# SOT23-3_to_AVR_Parttester.net
KiCad netlist of a schematic drawn in EAGLE
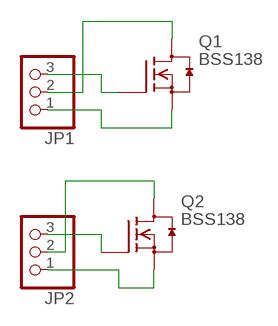
[diagram p0: schematic, sheet 1]

(export (version "E")
  (design (tool "Eeschema 10.0.6"))
  (components
    (comp (ref "JP1")
      (value "PINHD-1X3")
      (footprint "eagle-import:1X03")
      (libsource (lib "eagle-import") (part "PINHD-1X3"))
    )
    (comp (ref "JP2")
      (value "PINHD-1X3")
      (footprint "eagle-import:1X03")
      (libsource (lib "eagle-import") (part "PINHD-1X3"))
    )
    (comp (ref "Q1")
      (value "BSS138")
      (footprint "eagle-import:SOT23")
      (libsource (lib "eagle-import") (part "BSS138"))
    )
    (comp (ref "Q2")
      (value "BSS138")
      (footprint "eagle-import:SOT23")
      (libsource (lib "eagle-import") (part "BSS138"))
    )
  )
  (nets
    (net (code "1") (name "Net-(Q1-D)") (class "Default")
      (node (ref "JP1") (pin "2") (pinfunction "2_2") (pintype "passive"))
      (node (ref "Q1") (pin "3") (pinfunction "D_3") (pintype "passive"))
    )
    (net (code "2") (name "Net-(Q1-G)") (class "Default")
      (node (ref "JP1") (pin "3") (pinfunction "3_3") (pintype "passive"))
      (node (ref "Q1") (pin "1") (pinfunction "G_1") (pintype "passive"))
    )
    (net (code "3") (name "Net-(Q1-S)") (class "Default")
      (node (ref "JP1") (pin "1") (pinfunction "1_1") (pintype "passive"))
      (node (ref "Q1") (pin "2") (pinfunction "S_2") (pintype "passive"))
    )
    (net (code "4") (name "Net-(Q2-D)") (class "Default")
      (node (ref "JP2") (pin "2") (pinfunction "2_2") (pintype "passive"))
      (node (ref "Q2") (pin "3") (pinfunction "D_3") (pintype "passive"))
    )
    (net (code "5") (name "Net-(Q2-G)") (class "Default")
      (node (ref "JP2") (pin "3") (pinfunction "3_3") (pintype "passive"))
      (node (ref "Q2") (pin "1") (pinfunction "G_1") (pintype "passive"))
    )
    (net (code "6") (name "Net-(Q2-S)") (class "Default")
      (node (ref "JP2") (pin "1") (pinfunction "1_1") (pintype "passive"))
      (node (ref "Q2") (pin "2") (pinfunction "S_2") (pintype "passive"))
    )
  )
)
